# detector328p.net
KiCad netlist of a schematic drawn in EAGLE
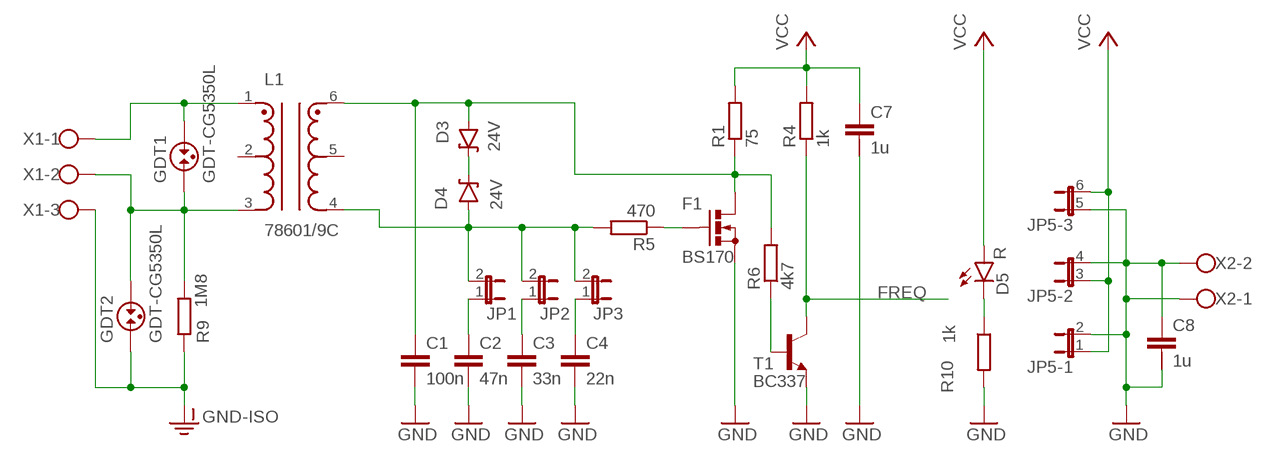
[diagram p0: schematic, sheet 1]
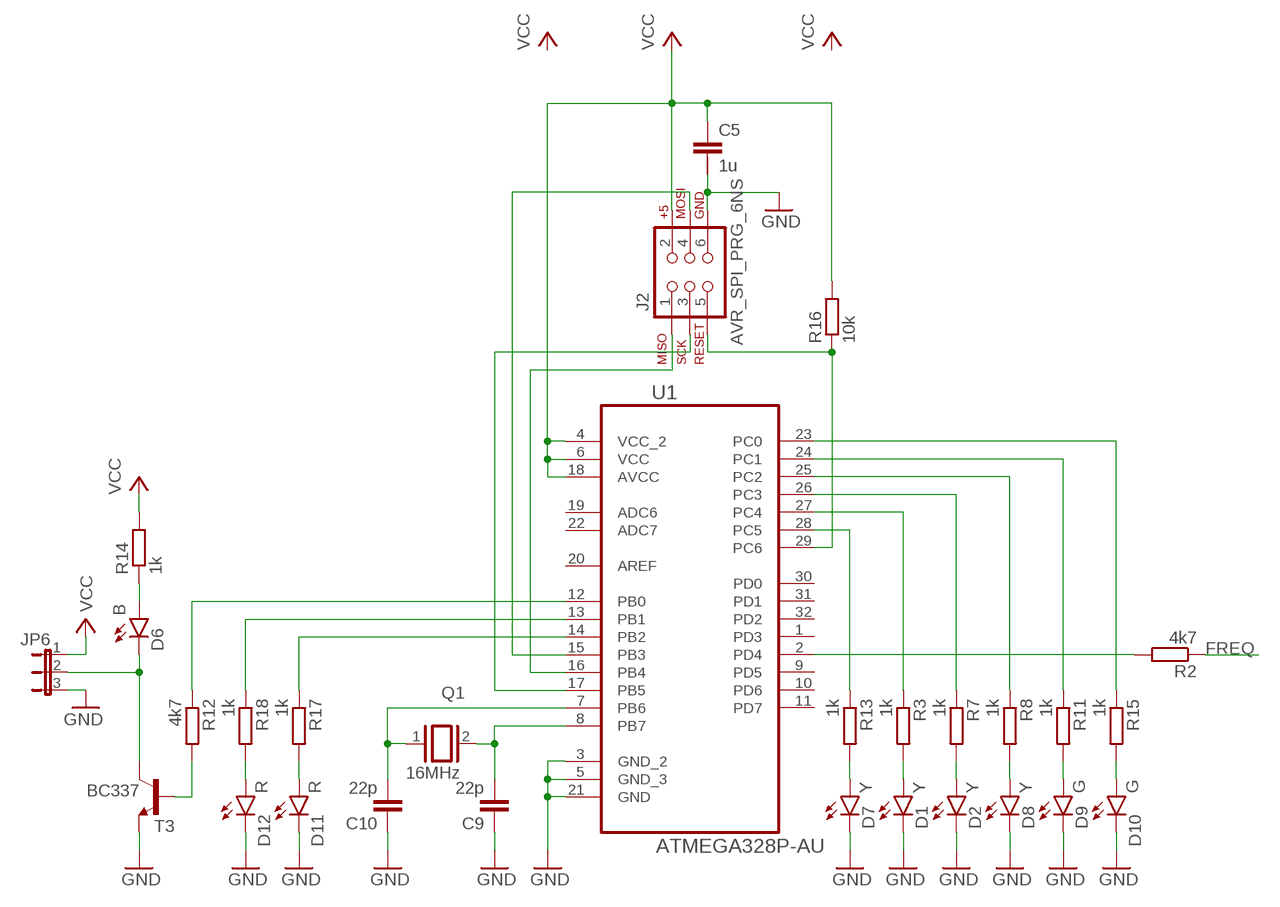
[diagram p1: schematic, sheet 2]

(export (version "E")
  (design (tool "Eeschema 10.0.6"))
  (components
    (comp (ref "C1")
      (value "100n")
      (footprint "eagle-import:C050-024X044")
      (libsource (lib "eagle-import") (part "C-EU050-024X044"))
    )
    (comp (ref "C2")
      (value "47n")
      (footprint "eagle-import:C050-024X044")
      (libsource (lib "eagle-import") (part "C-EU050-024X044"))
    )
    (comp (ref "C3")
      (value "33n")
      (footprint "eagle-import:C050-024X044")
      (libsource (lib "eagle-import") (part "C-EU050-024X044"))
    )
    (comp (ref "C4")
      (value "22n")
      (footprint "eagle-import:C050-024X044")
      (libsource (lib "eagle-import") (part "C-EU050-024X044"))
    )
    (comp (ref "C7")
      (value "1u")
      (footprint "eagle-import:C2.5_5-4")
      (libsource (lib "eagle-import") (part "C-2.5-5/4"))
    )
    (comp (ref "C8")
      (value "1u")
      (footprint "eagle-import:C2.5_5-4")
      (libsource (lib "eagle-import") (part "C-2.5-5/4"))
    )
    (comp (ref "D3")
      (value "24V")
      (footprint "eagle-import:DIODE-BZT52")
      (libsource (lib "eagle-import") (part "DIODE-ZENER"))
    )
    (comp (ref "D4")
      (value "24V")
      (footprint "eagle-import:DIODE-BZT52")
      (libsource (lib "eagle-import") (part "DIODE-ZENER"))
    )
    (comp (ref "D5")
      (value "R")
      (footprint "eagle-import:LED3MM")
      (libsource (lib "eagle-import") (part "LED3MM"))
    )
    (comp (ref "F1")
      (value "BS170")
      (footprint "eagle-import:SOT54E")
      (libsource (lib "eagle-import") (part "BS170"))
    )
    (comp (ref "GDT1")
      (value "GDT-CG5350L")
      (footprint "eagle-import:CG5350L")
      (libsource (lib "eagle-import") (part "GDT-CG5350L"))
    )
    (comp (ref "GDT2")
      (value "GDT-CG5350L")
      (footprint "eagle-import:CG5350L")
      (libsource (lib "eagle-import") (part "GDT-CG5350L"))
    )
    (comp (ref "JP1")
      (value "JUMPER-2PTH")
      (footprint "eagle-import:1X02")
      (libsource (lib "eagle-import") (part "JUMPER-2PTH"))
    )
    (comp (ref "JP2")
      (value "JUMPER-2PTH")
      (footprint "eagle-import:1X02")
      (libsource (lib "eagle-import") (part "JUMPER-2PTH"))
    )
    (comp (ref "JP3")
      (value "JUMPER-2PTH")
      (footprint "eagle-import:1X02")
      (libsource (lib "eagle-import") (part "JUMPER-2PTH"))
    )
    (comp (ref "JP5")
      (value "JP3QE")
      (footprint "eagle-import:JP3Q")
      (libsource (lib "eagle-import") (part "JP3QE"))
    )
    (comp (ref "L1")
      (value "78601/9C")
      (footprint "eagle-import:78601_9C")
      (libsource (lib "eagle-import") (part "78601/9C"))
    )
    (comp (ref "R1")
      (value "75")
      (footprint "eagle-import:0204_7")
      (libsource (lib "eagle-import") (part "R-EU_0204/7"))
    )
    (comp (ref "R4")
      (value "1k")
      (footprint "eagle-import:0204_5")
      (libsource (lib "eagle-import") (part "R-EU_0204/5"))
    )
    (comp (ref "R5")
      (value "470")
      (footprint "eagle-import:0204_5")
      (libsource (lib "eagle-import") (part "R-EU_0204/5"))
    )
    (comp (ref "R6")
      (value "4k7")
      (footprint "eagle-import:0204_5")
      (libsource (lib "eagle-import") (part "R-EU_0204/5"))
    )
    (comp (ref "R9")
      (value "1M8")
      (footprint "eagle-import:0204_5")
      (libsource (lib "eagle-import") (part "R-EU_0204/5"))
    )
    (comp (ref "R10")
      (value "1k")
      (footprint "eagle-import:0204_5")
      (libsource (lib "eagle-import") (part "R-EU_0204/5"))
    )
    (comp (ref "T1")
      (value "BC337")
      (footprint "eagle-import:TO92-CBE")
      (libsource (lib "eagle-import") (part "-NPN-TO92-CBEBC337"))
    )
    (comp (ref "X1")
      (value "W237-103")
      (footprint "eagle-import:W237-103")
      (fields (field (name "MPN") "237-103"))
      (libsource (lib "eagle-import") (part "W237-103"))
    )
    (comp (ref "X2")
      (value "W237-102")
      (footprint "eagle-import:W237-102")
      (fields (field (name "MPN") "237-102"))
      (libsource (lib "eagle-import") (part "W237-102"))
    )
    (comp (ref "C5")
      (value "1u")
      (footprint "eagle-import:C2.5_5-4")
      (libsource (lib "eagle-import") (part "C-2.5-5/4"))
    )
    (comp (ref "C9")
      (value "22p")
      (footprint "eagle-import:C050-024X044")
      (libsource (lib "eagle-import") (part "C-EU050-024X044"))
    )
    (comp (ref "C10")
      (value "22p")
      (footprint "eagle-import:C050-024X044")
      (libsource (lib "eagle-import") (part "C-EU050-024X044"))
    )
    (comp (ref "D1")
      (value "Y")
      (footprint "eagle-import:LED3MM")
      (libsource (lib "eagle-import") (part "LED3MM"))
    )
    (comp (ref "D2")
      (value "Y")
      (footprint "eagle-import:LED3MM")
      (libsource (lib "eagle-import") (part "LED3MM"))
    )
    (comp (ref "D6")
      (value "B")
      (footprint "eagle-import:LED3MM")
      (libsource (lib "eagle-import") (part "LED3MM"))
    )
    (comp (ref "D7")
      (value "Y")
      (footprint "eagle-import:LED3MM")
      (libsource (lib "eagle-import") (part "LED3MM"))
    )
    (comp (ref "D8")
      (value "Y")
      (footprint "eagle-import:LED3MM")
      (libsource (lib "eagle-import") (part "LED3MM"))
    )
    (comp (ref "D9")
      (value "G")
      (footprint "eagle-import:LED3MM")
      (libsource (lib "eagle-import") (part "LED3MM"))
    )
    (comp (ref "D10")
      (value "G")
      (footprint "eagle-import:LED3MM")
      (libsource (lib "eagle-import") (part "LED3MM"))
    )
    (comp (ref "D11")
      (value "R")
      (footprint "eagle-import:LED3MM")
      (libsource (lib "eagle-import") (part "LED3MM"))
    )
    (comp (ref "D12")
      (value "R")
      (footprint "eagle-import:LED3MM")
      (libsource (lib "eagle-import") (part "LED3MM"))
    )
    (comp (ref "J2")
      (value "AVR_SPI_PRG_6NS")
      (footprint "eagle-import:2X3-NS")
      (libsource (lib "eagle-import") (part "AVR_SPI_PRG_6NS"))
    )
    (comp (ref "JP6")
      (value "JP2E")
      (footprint "eagle-import:JP2")
      (libsource (lib "eagle-import") (part "JP2E"))
    )
    (comp (ref "Q1")
      (value "16MHz")
      (footprint "eagle-import:QS")
      (libsource (lib "eagle-import") (part "XTAL/S"))
    )
    (comp (ref "R2")
      (value "4k7")
      (footprint "eagle-import:0204_5")
      (libsource (lib "eagle-import") (part "R-EU_0204/5"))
    )
    (comp (ref "R3")
      (value "1k")
      (footprint "eagle-import:0204_5")
      (libsource (lib "eagle-import") (part "R-EU_0204/5"))
    )
    (comp (ref "R7")
      (value "1k")
      (footprint "eagle-import:0204_5")
      (libsource (lib "eagle-import") (part "R-EU_0204/5"))
    )
    (comp (ref "R8")
      (value "1k")
      (footprint "eagle-import:0204_5")
      (libsource (lib "eagle-import") (part "R-EU_0204/5"))
    )
    (comp (ref "R11")
      (value "1k")
      (footprint "eagle-import:0204_5")
      (libsource (lib "eagle-import") (part "R-EU_0204/5"))
    )
    (comp (ref "R12")
      (value "4k7")
      (footprint "eagle-import:0204_5")
      (libsource (lib "eagle-import") (part "R-EU_0204/5"))
    )
    (comp (ref "R13")
      (value "1k")
      (footprint "eagle-import:0204_5")
      (libsource (lib "eagle-import") (part "R-EU_0204/5"))
    )
    (comp (ref "R14")
      (value "1k")
      (footprint "eagle-import:0204_5")
      (libsource (lib "eagle-import") (part "R-EU_0204/5"))
    )
    (comp (ref "R15")
      (value "1k")
      (footprint "eagle-import:0204_5")
      (libsource (lib "eagle-import") (part "R-EU_0204/5"))
    )
    (comp (ref "R16")
      (value "10k")
      (footprint "eagle-import:0204_5")
      (libsource (lib "eagle-import") (part "R-EU_0204/5"))
    )
    (comp (ref "R17")
      (value "1k")
      (footprint "eagle-import:0204_5")
      (libsource (lib "eagle-import") (part "R-EU_0204/5"))
    )
    (comp (ref "R18")
      (value "1k")
      (footprint "eagle-import:0204_5")
      (libsource (lib "eagle-import") (part "R-EU_0204/5"))
    )
    (comp (ref "T3")
      (value "BC337")
      (footprint "eagle-import:TO92-CBE")
      (libsource (lib "eagle-import") (part "-NPN-TO92-CBEBC337"))
    )
    (comp (ref "U1")
      (value "ATMEGA328P-AU")
      (footprint "eagle-import:QFP80P900X900X120-32N")
      (libsource (lib "eagle-import") (part "ATMEGA328P-AU"))
    )
  )
  (nets
    (net (code "1") (name "FREQ") (class "Default")
      (node (ref "R2") (pin "1") (pinfunction "1_1") (pintype "passive"))
      (node (ref "R4") (pin "1") (pinfunction "1_1") (pintype "passive"))
      (node (ref "T1") (pin "C") (pinfunction "C_C") (pintype "passive"))
    )
    (net (code "2") (name "GND") (class "Default")
      (node (ref "C1") (pin "2") (pinfunction "2_2") (pintype "passive"))
      (node (ref "C10") (pin "1") (pinfunction "1_1") (pintype "passive"))
      (node (ref "C2") (pin "2") (pinfunction "2_2") (pintype "passive"))
      (node (ref "C3") (pin "2") (pinfunction "2_2") (pintype "passive"))
      (node (ref "C4") (pin "2") (pinfunction "2_2") (pintype "passive"))
      (node (ref "C5") (pin "2") (pinfunction "2_2") (pintype "passive"))
      (node (ref "C7") (pin "2") (pinfunction "2_2") (pintype "passive"))
      (node (ref "C8") (pin "1") (pinfunction "1_1") (pintype "passive"))
      (node (ref "C8") (pin "2") (pinfunction "2_2") (pintype "passive"))
      (node (ref "C9") (pin "1") (pinfunction "1_1") (pintype "passive"))
      (node (ref "D1") (pin "K") (pinfunction "C_K") (pintype "passive"))
      (node (ref "D10") (pin "K") (pinfunction "C_K") (pintype "passive"))
      (node (ref "D11") (pin "K") (pinfunction "C_K") (pintype "passive"))
      (node (ref "D12") (pin "K") (pinfunction "C_K") (pintype "passive"))
      (node (ref "D2") (pin "K") (pinfunction "C_K") (pintype "passive"))
      (node (ref "D7") (pin "K") (pinfunction "C_K") (pintype "passive"))
      (node (ref "D8") (pin "K") (pinfunction "C_K") (pintype "passive"))
      (node (ref "D9") (pin "K") (pinfunction "C_K") (pintype "passive"))
      (node (ref "F1") (pin "S") (pinfunction "S_S") (pintype "passive"))
      (node (ref "J2") (pin "6") (pinfunction "6_6") (pintype "passive"))
      (node (ref "JP5") (pin "2") (pinfunction "2_2") (pintype "passive"))
      (node (ref "JP5") (pin "4") (pinfunction "2_4") (pintype "passive"))
      (node (ref "JP5") (pin "5") (pinfunction "1_5") (pintype "passive"))
      (node (ref "JP6") (pin "3") (pinfunction "3_3") (pintype "passive"))
      (node (ref "R10") (pin "2") (pinfunction "2_2") (pintype "passive"))
      (node (ref "T1") (pin "E") (pinfunction "E_E") (pintype "passive"))
      (node (ref "T3") (pin "E") (pinfunction "E_E") (pintype "passive"))
      (node (ref "U1") (pin "21") (pinfunction "GND_21") (pintype "passive"))
      (node (ref "U1") (pin "3") (pinfunction "GND_2_3") (pintype "passive"))
      (node (ref "U1") (pin "5") (pinfunction "GND_3_5") (pintype "passive"))
      (node (ref "X2") (pin "1") (pinfunction "KL_1") (pintype "passive"))
      (node (ref "X2") (pin "2") (pinfunction "KL_2") (pintype "passive"))
    )
    (net (code "3") (name "GND-ISO") (class "Default")
      (node (ref "GDT2") (pin "1") (pinfunction "1_1") (pintype "passive"))
      (node (ref "R9") (pin "1") (pinfunction "1_1") (pintype "passive"))
      (node (ref "X1") (pin "3") (pinfunction "KL_3") (pintype "passive"))
    )
    (net (code "4") (name "Net-(C1-Pad1)") (class "Default")
      (node (ref "C1") (pin "1") (pinfunction "1_1") (pintype "passive"))
      (node (ref "D3") (pin "A") (pinfunction "A_A") (pintype "passive"))
      (node (ref "F1") (pin "D") (pinfunction "D_D") (pintype "passive"))
      (node (ref "L1") (pin "6") (pinfunction "6_6") (pintype "passive"))
      (node (ref "R1") (pin "1") (pinfunction "1_1") (pintype "passive"))
      (node (ref "R6") (pin "2") (pinfunction "2_2") (pintype "passive"))
    )
    (net (code "5") (name "Net-(C2-Pad1)") (class "Default")
      (node (ref "C2") (pin "1") (pinfunction "1_1") (pintype "passive"))
      (node (ref "JP1") (pin "1") (pinfunction "1_1") (pintype "passive"))
    )
    (net (code "6") (name "Net-(C3-Pad1)") (class "Default")
      (node (ref "C3") (pin "1") (pinfunction "1_1") (pintype "passive"))
      (node (ref "JP2") (pin "1") (pinfunction "1_1") (pintype "passive"))
    )
    (net (code "7") (name "Net-(C4-Pad1)") (class "Default")
      (node (ref "C4") (pin "1") (pinfunction "1_1") (pintype "passive"))
      (node (ref "JP3") (pin "1") (pinfunction "1_1") (pintype "passive"))
    )
    (net (code "8") (name "Net-(D1-PadA)") (class "Default")
      (node (ref "D1") (pin "A") (pinfunction "A_A") (pintype "passive"))
      (node (ref "R3") (pin "2") (pinfunction "2_2") (pintype "passive"))
    )
    (net (code "9") (name "Net-(D2-PadA)") (class "Default")
      (node (ref "D2") (pin "A") (pinfunction "A_A") (pintype "passive"))
      (node (ref "R7") (pin "2") (pinfunction "2_2") (pintype "passive"))
    )
    (net (code "10") (name "Net-(D3-PadC)") (class "Default")
      (node (ref "D3") (pin "C") (pinfunction "C_C") (pintype "passive"))
      (node (ref "D4") (pin "C") (pinfunction "C_C") (pintype "passive"))
    )
    (net (code "11") (name "Net-(D4-PadA)") (class "Default")
      (node (ref "D4") (pin "A") (pinfunction "A_A") (pintype "passive"))
      (node (ref "JP1") (pin "2") (pinfunction "2_2") (pintype "passive"))
      (node (ref "JP2") (pin "2") (pinfunction "2_2") (pintype "passive"))
      (node (ref "JP3") (pin "2") (pinfunction "2_2") (pintype "passive"))
      (node (ref "L1") (pin "4") (pinfunction "4_4") (pintype "passive"))
      (node (ref "R5") (pin "2") (pinfunction "2_2") (pintype "passive"))
    )
    (net (code "12") (name "Net-(D5-C)") (class "Default")
      (node (ref "D5") (pin "K") (pinfunction "C_K") (pintype "passive"))
      (node (ref "R10") (pin "1") (pinfunction "1_1") (pintype "passive"))
    )
    (net (code "13") (name "Net-(D6-C)") (class "Default")
      (node (ref "D6") (pin "K") (pinfunction "C_K") (pintype "passive"))
      (node (ref "JP6") (pin "2") (pinfunction "2_2") (pintype "passive"))
      (node (ref "T3") (pin "C") (pinfunction "C_C") (pintype "passive"))
    )
    (net (code "14") (name "Net-(D6-PadA)") (class "Default")
      (node (ref "D6") (pin "A") (pinfunction "A_A") (pintype "passive"))
      (node (ref "R14") (pin "1") (pinfunction "1_1") (pintype "passive"))
    )
    (net (code "15") (name "Net-(D7-PadA)") (class "Default")
      (node (ref "D7") (pin "A") (pinfunction "A_A") (pintype "passive"))
      (node (ref "R13") (pin "2") (pinfunction "2_2") (pintype "passive"))
    )
    (net (code "16") (name "Net-(D8-PadA)") (class "Default")
      (node (ref "D8") (pin "A") (pinfunction "A_A") (pintype "passive"))
      (node (ref "R8") (pin "2") (pinfunction "2_2") (pintype "passive"))
    )
    (net (code "17") (name "Net-(D9-PadA)") (class "Default")
      (node (ref "D9") (pin "A") (pinfunction "A_A") (pintype "passive"))
      (node (ref "R11") (pin "2") (pinfunction "2_2") (pintype "passive"))
    )
    (net (code "18") (name "Net-(D10-PadA)") (class "Default")
      (node (ref "D10") (pin "A") (pinfunction "A_A") (pintype "passive"))
      (node (ref "R15") (pin "2") (pinfunction "2_2") (pintype "passive"))
    )
    (net (code "19") (name "Net-(D11-PadA)") (class "Default")
      (node (ref "D11") (pin "A") (pinfunction "A_A") (pintype "passive"))
      (node (ref "R17") (pin "2") (pinfunction "2_2") (pintype "passive"))
    )
    (net (code "20") (name "Net-(D12-PadA)") (class "Default")
      (node (ref "D12") (pin "A") (pinfunction "A_A") (pintype "passive"))
      (node (ref "R18") (pin "2") (pinfunction "2_2") (pintype "passive"))
    )
    (net (code "21") (name "Net-(F1-PadG)") (class "Default")
      (node (ref "F1") (pin "G") (pinfunction "G_G") (pintype "passive"))
      (node (ref "R5") (pin "1") (pinfunction "1_1") (pintype "passive"))
    )
    (net (code "22") (name "Net-(R6-Pad1)") (class "Default")
      (node (ref "R6") (pin "1") (pinfunction "1_1") (pintype "passive"))
      (node (ref "T1") (pin "B") (pinfunction "B_B") (pintype "passive"))
    )
    (net (code "23") (name "Net-(R12-Pad2)") (class "Default")
      (node (ref "R12") (pin "2") (pinfunction "2_2") (pintype "passive"))
      (node (ref "T3") (pin "B") (pinfunction "B_B") (pintype "passive"))
    )
    (net (code "24") (name "Net-(U1-PB0)") (class "Default")
      (node (ref "R12") (pin "1") (pinfunction "1_1") (pintype "passive"))
      (node (ref "U1") (pin "12") (pinfunction "PB0_12") (pintype "bidirectional"))
    )
    (net (code "25") (name "Net-(U1-PB1)") (class "Default")
      (node (ref "R18") (pin "1") (pinfunction "1_1") (pintype "passive"))
      (node (ref "U1") (pin "13") (pinfunction "PB1_13") (pintype "bidirectional"))
    )
    (net (code "26") (name "Net-(U1-PB2)") (class "Default")
      (node (ref "R17") (pin "1") (pinfunction "1_1") (pintype "passive"))
      (node (ref "U1") (pin "14") (pinfunction "PB2_14") (pintype "bidirectional"))
    )
    (net (code "27") (name "Net-(U1-PB3)") (class "Default")
      (node (ref "J2") (pin "4") (pinfunction "4_4") (pintype "passive"))
      (node (ref "U1") (pin "15") (pinfunction "PB3_15") (pintype "bidirectional"))
    )
    (net (code "28") (name "Net-(U1-PB4)") (class "Default")
      (node (ref "J2") (pin "1") (pinfunction "1_1") (pintype "passive"))
      (node (ref "U1") (pin "16") (pinfunction "PB4_16") (pintype "bidirectional"))
    )
    (net (code "29") (name "Net-(U1-PB5)") (class "Default")
      (node (ref "J2") (pin "3") (pinfunction "3_3") (pintype "passive"))
      (node (ref "U1") (pin "17") (pinfunction "PB5_17") (pintype "bidirectional"))
    )
    (net (code "30") (name "Net-(U1-PB6)") (class "Default")
      (node (ref "C10") (pin "2") (pinfunction "2_2") (pintype "passive"))
      (node (ref "Q1") (pin "1") (pinfunction "1_1") (pintype "passive"))
      (node (ref "U1") (pin "7") (pinfunction "PB6_7") (pintype "bidirectional"))
    )
    (net (code "31") (name "Net-(U1-PB7)") (class "Default")
      (node (ref "C9") (pin "2") (pinfunction "2_2") (pintype "passive"))
      (node (ref "Q1") (pin "2") (pinfunction "2_2") (pintype "passive"))
      (node (ref "U1") (pin "8") (pinfunction "PB7_8") (pintype "bidirectional"))
    )
    (net (code "32") (name "Net-(U1-PC0)") (class "Default")
      (node (ref "R15") (pin "1") (pinfunction "1_1") (pintype "passive"))
      (node (ref "U1") (pin "23") (pinfunction "PC0_23") (pintype "bidirectional"))
    )
    (net (code "33") (name "Net-(U1-PC1)") (class "Default")
      (node (ref "R11") (pin "1") (pinfunction "1_1") (pintype "passive"))
      (node (ref "U1") (pin "24") (pinfunction "PC1_24") (pintype "bidirectional"))
    )
    (net (code "34") (name "Net-(U1-PC2)") (class "Default")
      (node (ref "R8") (pin "1") (pinfunction "1_1") (pintype "passive"))
      (node (ref "U1") (pin "25") (pinfunction "PC2_25") (pintype "bidirectional"))
    )
    (net (code "35") (name "Net-(U1-PC3)") (class "Default")
      (node (ref "R7") (pin "1") (pinfunction "1_1") (pintype "passive"))
      (node (ref "U1") (pin "26") (pinfunction "PC3_26") (pintype "bidirectional"))
    )
    (net (code "36") (name "Net-(U1-PC4)") (class "Default")
      (node (ref "R3") (pin "1") (pinfunction "1_1") (pintype "passive"))
      (node (ref "U1") (pin "27") (pinfunction "PC4_27") (pintype "bidirectional"))
    )
    (net (code "37") (name "Net-(U1-PC5)") (class "Default")
      (node (ref "R13") (pin "1") (pinfunction "1_1") (pintype "passive"))
      (node (ref "U1") (pin "28") (pinfunction "PC5_28") (pintype "bidirectional"))
    )
    (net (code "38") (name "Net-(U1-PC6)") (class "Default")
      (node (ref "J2") (pin "5") (pinfunction "5_5") (pintype "passive"))
      (node (ref "R16") (pin "1") (pinfunction "1_1") (pintype "passive"))
      (node (ref "U1") (pin "29") (pinfunction "PC6_29") (pintype "bidirectional"))
    )
    (net (code "39") (name "Net-(U1-PD4)") (class "Default")
      (node (ref "R2") (pin "2") (pinfunction "2_2") (pintype "passive"))
      (node (ref "U1") (pin "2") (pinfunction "PD4_2") (pintype "bidirectional"))
    )
    (net (code "40") (name "Net-(X1A-KL)") (class "Default")
      (node (ref "GDT1") (pin "2") (pinfunction "2_2") (pintype "passive"))
      (node (ref "L1") (pin "1") (pinfunction "1_1") (pintype "passive"))
      (node (ref "X1") (pin "1") (pinfunction "KL_1") (pintype "passive"))
    )
    (net (code "41") (name "Net-(X1B-KL)") (class "Default")
      (node (ref "GDT1") (pin "1") (pinfunction "1_1") (pintype "passive"))
      (node (ref "GDT2") (pin "2") (pinfunction "2_2") (pintype "passive"))
      (node (ref "L1") (pin "3") (pinfunction "3_3") (pintype "passive"))
      (node (ref "R9") (pin "2") (pinfunction "2_2") (pintype "passive"))
      (node (ref "X1") (pin "2") (pinfunction "KL_2") (pintype "passive"))
    )
    (net (code "42") (name "VCC") (class "Default")
      (node (ref "C5") (pin "1") (pinfunction "1_1") (pintype "passive"))
      (node (ref "C7") (pin "1") (pinfunction "1_1") (pintype "passive"))
      (node (ref "D5") (pin "A") (pinfunction "A_A") (pintype "passive"))
      (node (ref "J2") (pin "2") (pinfunction "2_2") (pintype "passive"))
      (node (ref "JP5") (pin "1") (pinfunction "1_1") (pintype "passive"))
      (node (ref "JP5") (pin "3") (pinfunction "1_3") (pintype "passive"))
      (node (ref "JP5") (pin "6") (pinfunction "2_6") (pintype "passive"))
      (node (ref "JP6") (pin "1") (pinfunction "1_1") (pintype "passive"))
      (node (ref "R1") (pin "2") (pinfunction "2_2") (pintype "passive"))
      (node (ref "R14") (pin "2") (pinfunction "2_2") (pintype "passive"))
      (node (ref "R16") (pin "2") (pinfunction "2_2") (pintype "passive"))
      (node (ref "R4") (pin "2") (pinfunction "2_2") (pintype "passive"))
      (node (ref "U1") (pin "18") (pinfunction "AVCC_18") (pintype "power_in"))
      (node (ref "U1") (pin "4") (pinfunction "VCC_2_4") (pintype "power_in"))
      (node (ref "U1") (pin "6") (pinfunction "VCC_6") (pintype "power_in"))
    )
    (net (code "43") (name "unconnected-(C5-Pad3)") (class "Default")
      (node (ref "C5") (pin "3") (pinfunction "3_3") (pintype "passive"))
    )
    (net (code "44") (name "unconnected-(C7-Pad3)") (class "Default")
      (node (ref "C7") (pin "3") (pinfunction "3_3") (pintype "passive"))
    )
    (net (code "45") (name "unconnected-(C8-Pad3)") (class "Default")
      (node (ref "C8") (pin "3") (pinfunction "3_3") (pintype "passive"))
    )
    (net (code "46") (name "unconnected-(L1-Pad2)") (class "Default")
      (node (ref "L1") (pin "2") (pinfunction "2_2") (pintype "passive"))
    )
    (net (code "47") (name "unconnected-(L1-Pad5)") (class "Default")
      (node (ref "L1") (pin "5") (pinfunction "5_5") (pintype "passive"))
    )
    (net (code "48") (name "unconnected-(U1-ADC6-Pad19)") (class "Default")
      (node (ref "U1") (pin "19") (pinfunction "ADC6_19") (pintype "input"))
    )
    (net (code "49") (name "unconnected-(U1-ADC7-Pad22)") (class "Default")
      (node (ref "U1") (pin "22") (pinfunction "ADC7_22") (pintype "input"))
    )
    (net (code "50") (name "unconnected-(U1-AREF-Pad20)") (class "Default")
      (node (ref "U1") (pin "20") (pinfunction "AREF_20") (pintype "input"))
    )
    (net (code "51") (name "unconnected-(U1-PD0-Pad30)") (class "Default")
      (node (ref "U1") (pin "30") (pinfunction "PD0_30") (pintype "bidirectional"))
    )
    (net (code "52") (name "unconnected-(U1-PD1-Pad31)") (class "Default")
      (node (ref "U1") (pin "31") (pinfunction "PD1_31") (pintype "bidirectional"))
    )
    (net (code "53") (name "unconnected-(U1-PD2-Pad32)") (class "Default")
      (node (ref "U1") (pin "32") (pinfunction "PD2_32") (pintype "bidirectional"))
    )
    (net (code "54") (name "unconnected-(U1-PD3-Pad1)") (class "Default")
      (node (ref "U1") (pin "1") (pinfunction "PD3_1") (pintype "bidirectional"))
    )
    (net (code "55") (name "unconnected-(U1-PD5-Pad9)") (class "Default")
      (node (ref "U1") (pin "9") (pinfunction "PD5_9") (pintype "bidirectional"))
    )
    (net (code "56") (name "unconnected-(U1-PD6-Pad10)") (class "Default")
      (node (ref "U1") (pin "10") (pinfunction "PD6_10") (pintype "bidirectional"))
    )
    (net (code "57") (name "unconnected-(U1-PD7-Pad11)") (class "Default")
      (node (ref "U1") (pin "11") (pinfunction "PD7_11") (pintype "bidirectional"))
    )
  )
)
